# spt_interface_v4_withbattcheck.net
KiCad netlist of a schematic drawn in EAGLE
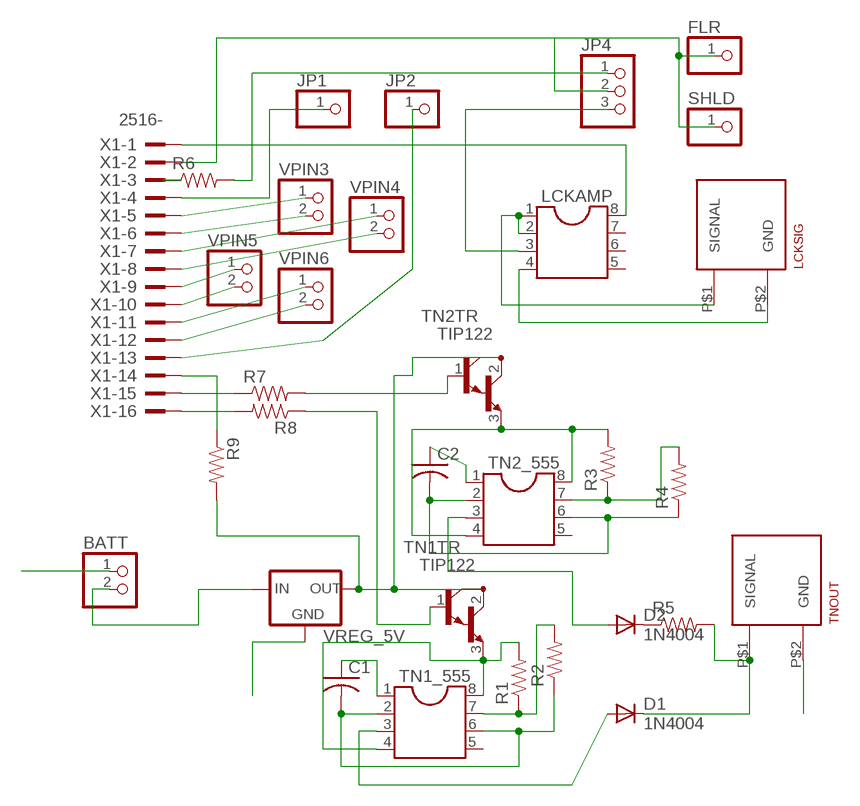
[diagram p0: schematic, sheet 1]

(export (version "E")
  (design (tool "Eeschema 10.0.6"))
  (components
    (comp (ref "BATT")
      (value "PINHD-1X2")
      (footprint "eagle-import:1X02")
      (libsource (lib "eagle-import") (part "PINHD-1X2"))
    )
    (comp (ref "C1")
      (value "C-US050-024X044")
      (footprint "eagle-import:C050-024X044")
      (libsource (lib "eagle-import") (part "C-US050-024X044"))
    )
    (comp (ref "C2")
      (value "C-US050-024X044")
      (footprint "eagle-import:C050-024X044")
      (libsource (lib "eagle-import") (part "C-US050-024X044"))
    )
    (comp (ref "D1")
      (value "1N4004")
      (footprint "eagle-import:DO41-10")
      (libsource (lib "eagle-import") (part "1N4004"))
    )
    (comp (ref "D2")
      (value "1N4004")
      (footprint "eagle-import:DO41-10")
      (libsource (lib "eagle-import") (part "1N4004"))
    )
    (comp (ref "FLR")
      (value "PINHD-1X1")
      (footprint "eagle-import:1X01")
      (libsource (lib "eagle-import") (part "PINHD-1X1"))
    )
    (comp (ref "JP1")
      (value "PINHD-1X1")
      (footprint "eagle-import:1X01")
      (libsource (lib "eagle-import") (part "PINHD-1X1"))
    )
    (comp (ref "JP2")
      (value "PINHD-1X1")
      (footprint "eagle-import:1X01")
      (libsource (lib "eagle-import") (part "PINHD-1X1"))
    )
    (comp (ref "JP4")
      (value "PINHD-1X3")
      (footprint "eagle-import:1X03")
      (libsource (lib "eagle-import") (part "PINHD-1X3"))
    )
    (comp (ref "LCKAMP")
      (value "DIL8")
      (footprint "eagle-import:DIL08")
      (libsource (lib "eagle-import") (part "DIL8"))
    )
    (comp (ref "LCKSIG")
      (value "BNC_VERTICAL")
      (footprint "eagle-import:BNC_VERTICAL")
      (libsource (lib "eagle-import") (part "BNC_VERTICAL"))
    )
    (comp (ref "R1")
      (value "RESISTORPTH-1/2W")
      (footprint "eagle-import:AXIAL-0.5")
      (libsource (lib "eagle-import") (part "RESISTORPTH-1/2W"))
    )
    (comp (ref "R2")
      (value "RESISTORPTH-1/2W")
      (footprint "eagle-import:AXIAL-0.5")
      (libsource (lib "eagle-import") (part "RESISTORPTH-1/2W"))
    )
    (comp (ref "R3")
      (value "RESISTORPTH-1/2W")
      (footprint "eagle-import:AXIAL-0.5")
      (libsource (lib "eagle-import") (part "RESISTORPTH-1/2W"))
    )
    (comp (ref "R4")
      (value "RESISTORPTH-1/2W")
      (footprint "eagle-import:AXIAL-0.5")
      (libsource (lib "eagle-import") (part "RESISTORPTH-1/2W"))
    )
    (comp (ref "R5")
      (value "RESISTORPTH-1/2W")
      (footprint "eagle-import:AXIAL-0.5")
      (libsource (lib "eagle-import") (part "RESISTORPTH-1/2W"))
    )
    (comp (ref "R6")
      (value "RESISTORPTH-1/2W")
      (footprint "eagle-import:AXIAL-0.5")
      (libsource (lib "eagle-import") (part "RESISTORPTH-1/2W"))
    )
    (comp (ref "R7")
      (value "RESISTORPTH-1/2W")
      (footprint "eagle-import:AXIAL-0.5")
      (libsource (lib "eagle-import") (part "RESISTORPTH-1/2W"))
    )
    (comp (ref "R8")
      (value "RESISTORPTH-1/2W")
      (footprint "eagle-import:AXIAL-0.5")
      (libsource (lib "eagle-import") (part "RESISTORPTH-1/2W"))
    )
    (comp (ref "R9")
      (value "RESISTORPTH-1/2W")
      (footprint "eagle-import:AXIAL-0.5")
      (libsource (lib "eagle-import") (part "RESISTORPTH-1/2W"))
    )
    (comp (ref "SHLD")
      (value "PINHD-1X1")
      (footprint "eagle-import:1X01")
      (libsource (lib "eagle-import") (part "PINHD-1X1"))
    )
    (comp (ref "TN1TR")
      (value "TIP122")
      (footprint "eagle-import:TO220")
      (libsource (lib "eagle-import") (part "TIP122"))
    )
    (comp (ref "TN1_555")
      (value "DIL8")
      (footprint "eagle-import:DIL08")
      (libsource (lib "eagle-import") (part "DIL8"))
    )
    (comp (ref "TN2TR")
      (value "TIP122")
      (footprint "eagle-import:TO220")
      (libsource (lib "eagle-import") (part "TIP122"))
    )
    (comp (ref "TN2_555")
      (value "DIL8")
      (footprint "eagle-import:DIL08")
      (libsource (lib "eagle-import") (part "DIL8"))
    )
    (comp (ref "TNOUT")
      (value "BNC_VERTICAL")
      (footprint "eagle-import:BNC_VERTICAL")
      (libsource (lib "eagle-import") (part "BNC_VERTICAL"))
    )
    (comp (ref "VPIN3")
      (value "PINHD-1X2")
      (footprint "eagle-import:1X02")
      (libsource (lib "eagle-import") (part "PINHD-1X2"))
    )
    (comp (ref "VPIN4")
      (value "PINHD-1X2")
      (footprint "eagle-import:1X02")
      (libsource (lib "eagle-import") (part "PINHD-1X2"))
    )
    (comp (ref "VPIN5")
      (value "PINHD-1X2")
      (footprint "eagle-import:1X02")
      (libsource (lib "eagle-import") (part "PINHD-1X2"))
    )
    (comp (ref "VPIN6")
      (value "PINHD-1X2")
      (footprint "eagle-import:1X02")
      (libsource (lib "eagle-import") (part "PINHD-1X2"))
    )
    (comp (ref "VREG_5V")
      (value "78XXL")
      (footprint "eagle-import:78XXL")
      (libsource (lib "eagle-import") (part "78XXL"))
    )
    (comp (ref "X1")
      (value "2516-")
      (footprint "eagle-import:PAK100_2500-16")
      (libsource (lib "eagle-import") (part "2516-"))
    )
  )
  (nets
    (net (code "1") (name "/GND") (class "Default")
      (node (ref "BATT") (pin "1") (pinfunction "1_1") (pintype "passive"))
      (node (ref "C1") (pin "1") (pinfunction "1_1") (pintype "passive"))
      (node (ref "C2") (pin "1") (pinfunction "1_1") (pintype "passive"))
      (node (ref "FLR") (pin "1") (pinfunction "1_1") (pintype "passive"))
      (node (ref "JP4") (pin "2") (pinfunction "2_2") (pintype "passive"))
      (node (ref "LCKAMP") (pin "4") (pinfunction "4_4") (pintype "passive"))
      (node (ref "LCKSIG") (pin "P$2") (pinfunction "GND_P$2") (pintype "bidirectional"))
      (node (ref "SHLD") (pin "1") (pinfunction "1_1") (pintype "passive"))
      (node (ref "TN1_555") (pin "1") (pinfunction "1_1") (pintype "passive"))
      (node (ref "TN2_555") (pin "1") (pinfunction "1_1") (pintype "passive"))
      (node (ref "TNOUT") (pin "P$2") (pinfunction "GND_P$2") (pintype "bidirectional"))
      (node (ref "VREG_5V") (pin "GND") (pinfunction "GND_GND") (pintype "input"))
      (node (ref "X1") (pin "2") (pinfunction "KL_2") (pintype "passive"))
    )
    (net (code "2") (name "Net-(BATT-Pad2)") (class "Default")
      (node (ref "BATT") (pin "2") (pinfunction "2_2") (pintype "passive"))
      (node (ref "VREG_5V") (pin "IN") (pinfunction "IN_IN") (pintype "input"))
    )
    (net (code "3") (name "Net-(D1-PadA)") (class "Default")
      (node (ref "D1") (pin "A") (pinfunction "A_A") (pintype "passive"))
      (node (ref "TN1_555") (pin "3") (pinfunction "3_3") (pintype "passive"))
    )
    (net (code "4") (name "Net-(D2-PadA)") (class "Default")
      (node (ref "D2") (pin "A") (pinfunction "A_A") (pintype "passive"))
      (node (ref "TN2_555") (pin "3") (pinfunction "3_3") (pintype "passive"))
    )
    (net (code "5") (name "Net-(JP4-Pad3)") (class "Default")
      (node (ref "JP4") (pin "3") (pinfunction "3_3") (pintype "passive"))
      (node (ref "LCKAMP") (pin "3") (pinfunction "3_3") (pintype "passive"))
    )
    (net (code "6") (name "Net-(LCKSIG-SIGNAL)") (class "Default")
      (node (ref "LCKAMP") (pin "1") (pinfunction "1_1") (pintype "passive"))
      (node (ref "LCKAMP") (pin "2") (pinfunction "2_2") (pintype "passive"))
      (node (ref "LCKSIG") (pin "P$1") (pinfunction "SIGNAL_P$1") (pintype "bidirectional"))
    )
    (net (code "7") (name "Net-(R1-1)") (class "Default")
      (node (ref "R1") (pin "P$1") (pinfunction "1_P$1") (pintype "passive"))
      (node (ref "R2") (pin "P$2") (pinfunction "2_P$2") (pintype "passive"))
      (node (ref "TN1_555") (pin "7") (pinfunction "7_7") (pintype "passive"))
    )
    (net (code "8") (name "Net-(R1-2)") (class "Default")
      (node (ref "R1") (pin "P$2") (pinfunction "2_P$2") (pintype "passive"))
      (node (ref "TN1TR") (pin "3") (pinfunction "E_3") (pintype "passive"))
      (node (ref "TN1_555") (pin "4") (pinfunction "4_4") (pintype "passive"))
      (node (ref "TN1_555") (pin "8") (pinfunction "8_8") (pintype "passive"))
    )
    (net (code "9") (name "Net-(R2-1)") (class "Default")
      (node (ref "C1") (pin "2") (pinfunction "2_2") (pintype "passive"))
      (node (ref "R2") (pin "P$1") (pinfunction "1_P$1") (pintype "passive"))
      (node (ref "TN1_555") (pin "2") (pinfunction "2_2") (pintype "passive"))
      (node (ref "TN1_555") (pin "6") (pinfunction "6_6") (pintype "passive"))
    )
    (net (code "10") (name "Net-(R3-1)") (class "Default")
      (node (ref "R3") (pin "P$1") (pinfunction "1_P$1") (pintype "passive"))
      (node (ref "R4") (pin "P$2") (pinfunction "2_P$2") (pintype "passive"))
      (node (ref "TN2_555") (pin "7") (pinfunction "7_7") (pintype "passive"))
    )
    (net (code "11") (name "Net-(R3-2)") (class "Default")
      (node (ref "R3") (pin "P$2") (pinfunction "2_P$2") (pintype "passive"))
      (node (ref "TN2TR") (pin "3") (pinfunction "E_3") (pintype "passive"))
      (node (ref "TN2_555") (pin "4") (pinfunction "4_4") (pintype "passive"))
      (node (ref "TN2_555") (pin "8") (pinfunction "8_8") (pintype "passive"))
    )
    (net (code "12") (name "Net-(R4-1)") (class "Default")
      (node (ref "C2") (pin "2") (pinfunction "2_2") (pintype "passive"))
      (node (ref "R4") (pin "P$1") (pinfunction "1_P$1") (pintype "passive"))
      (node (ref "TN2_555") (pin "2") (pinfunction "2_2") (pintype "passive"))
      (node (ref "TN2_555") (pin "6") (pinfunction "6_6") (pintype "passive"))
    )
    (net (code "13") (name "Net-(R5-1)") (class "Default")
      (node (ref "D2") (pin "C") (pinfunction "C_C") (pintype "passive"))
      (node (ref "R5") (pin "P$1") (pinfunction "1_P$1") (pintype "passive"))
    )
    (net (code "14") (name "Net-(R5-2)") (class "Default")
      (node (ref "D1") (pin "C") (pinfunction "C_C") (pintype "passive"))
      (node (ref "R5") (pin "P$2") (pinfunction "2_P$2") (pintype "passive"))
      (node (ref "TNOUT") (pin "P$1") (pinfunction "SIGNAL_P$1") (pintype "bidirectional"))
    )
    (net (code "15") (name "Net-(R6-1)") (class "Default")
      (node (ref "R6") (pin "P$1") (pinfunction "1_P$1") (pintype "passive"))
      (node (ref "X1") (pin "3") (pinfunction "KL_3") (pintype "passive"))
    )
    (net (code "16") (name "Net-(R6-2)") (class "Default")
      (node (ref "JP4") (pin "1") (pinfunction "1_1") (pintype "passive"))
      (node (ref "R6") (pin "P$2") (pinfunction "2_P$2") (pintype "passive"))
    )
    (net (code "17") (name "Net-(R7-1)") (class "Default")
      (node (ref "R7") (pin "P$1") (pinfunction "1_P$1") (pintype "passive"))
      (node (ref "X1") (pin "15") (pinfunction "KL_15") (pintype "passive"))
    )
    (net (code "18") (name "Net-(R7-2)") (class "Default")
      (node (ref "R7") (pin "P$2") (pinfunction "2_P$2") (pintype "passive"))
      (node (ref "TN2TR") (pin "1") (pinfunction "B_1") (pintype "passive"))
    )
    (net (code "19") (name "Net-(R8-1)") (class "Default")
      (node (ref "R8") (pin "P$1") (pinfunction "1_P$1") (pintype "passive"))
      (node (ref "TN1TR") (pin "1") (pinfunction "B_1") (pintype "passive"))
    )
    (net (code "20") (name "Net-(R8-2)") (class "Default")
      (node (ref "R8") (pin "P$2") (pinfunction "2_P$2") (pintype "passive"))
      (node (ref "X1") (pin "16") (pinfunction "KL_16") (pintype "passive"))
    )
    (net (code "21") (name "Net-(R9-1)") (class "Default")
      (node (ref "R9") (pin "P$1") (pinfunction "1_P$1") (pintype "passive"))
      (node (ref "X1") (pin "14") (pinfunction "KL_14") (pintype "passive"))
    )
    (net (code "22") (name "Net-(R9-2)") (class "Default")
      (node (ref "R9") (pin "P$2") (pinfunction "2_P$2") (pintype "passive"))
      (node (ref "TN1TR") (pin "2") (pinfunction "C_2") (pintype "passive"))
      (node (ref "TN2TR") (pin "2") (pinfunction "C_2") (pintype "passive"))
      (node (ref "VREG_5V") (pin "OUT") (pinfunction "OUT_OUT") (pintype "passive"))
    )
    (net (code "23") (name "Net-(X1A-KL)") (class "Default")
      (node (ref "LCKAMP") (pin "8") (pinfunction "8_8") (pintype "passive"))
      (node (ref "X1") (pin "1") (pinfunction "KL_1") (pintype "passive"))
    )
    (net (code "24") (name "Net-(X1B-KL)") (class "Default")
      (node (ref "VPIN5") (pin "2") (pinfunction "2_2") (pintype "passive"))
      (node (ref "X1") (pin "10") (pinfunction "KL_10") (pintype "passive"))
    )
    (net (code "25") (name "Net-(X1C-KL)") (class "Default")
      (node (ref "VPIN6") (pin "1") (pinfunction "1_1") (pintype "passive"))
      (node (ref "X1") (pin "11") (pinfunction "KL_11") (pintype "passive"))
    )
    (net (code "26") (name "Net-(X1D-KL)") (class "Default")
      (node (ref "VPIN6") (pin "2") (pinfunction "2_2") (pintype "passive"))
      (node (ref "X1") (pin "12") (pinfunction "KL_12") (pintype "passive"))
    )
    (net (code "27") (name "Net-(X1E-KL)") (class "Default")
      (node (ref "JP2") (pin "1") (pinfunction "1_1") (pintype "passive"))
      (node (ref "X1") (pin "13") (pinfunction "KL_13") (pintype "passive"))
    )
    (net (code "28") (name "Net-(X1K-KL)") (class "Default")
      (node (ref "JP1") (pin "1") (pinfunction "1_1") (pintype "passive"))
      (node (ref "X1") (pin "4") (pinfunction "KL_4") (pintype "passive"))
    )
    (net (code "29") (name "Net-(X1L-KL)") (class "Default")
      (node (ref "VPIN3") (pin "1") (pinfunction "1_1") (pintype "passive"))
      (node (ref "X1") (pin "5") (pinfunction "KL_5") (pintype "passive"))
    )
    (net (code "30") (name "Net-(X1M-KL)") (class "Default")
      (node (ref "VPIN3") (pin "2") (pinfunction "2_2") (pintype "passive"))
      (node (ref "X1") (pin "6") (pinfunction "KL_6") (pintype "passive"))
    )
    (net (code "31") (name "Net-(X1N-KL)") (class "Default")
      (node (ref "VPIN4") (pin "1") (pinfunction "1_1") (pintype "passive"))
      (node (ref "X1") (pin "7") (pinfunction "KL_7") (pintype "passive"))
    )
    (net (code "32") (name "Net-(X1O-KL)") (class "Default")
      (node (ref "VPIN4") (pin "2") (pinfunction "2_2") (pintype "passive"))
      (node (ref "X1") (pin "8") (pinfunction "KL_8") (pintype "passive"))
    )
    (net (code "33") (name "Net-(X1P-KL)") (class "Default")
      (node (ref "VPIN5") (pin "1") (pinfunction "1_1") (pintype "passive"))
      (node (ref "X1") (pin "9") (pinfunction "KL_9") (pintype "passive"))
    )
    (net (code "34") (name "unconnected-(LCKAMP-Pad5)") (class "Default")
      (node (ref "LCKAMP") (pin "5") (pinfunction "5_5") (pintype "passive"))
    )
    (net (code "35") (name "unconnected-(LCKAMP-Pad6)") (class "Default")
      (node (ref "LCKAMP") (pin "6") (pinfunction "6_6") (pintype "passive"))
    )
    (net (code "36") (name "unconnected-(LCKAMP-Pad7)") (class "Default")
      (node (ref "LCKAMP") (pin "7") (pinfunction "7_7") (pintype "passive"))
    )
    (net (code "37") (name "unconnected-(TN1_555-Pad5)") (class "Default")
      (node (ref "TN1_555") (pin "5") (pinfunction "5_5") (pintype "passive"))
    )
    (net (code "38") (name "unconnected-(TN2_555-Pad5)") (class "Default")
      (node (ref "TN2_555") (pin "5") (pinfunction "5_5") (pintype "passive"))
    )
  )
)
